# USB-C-Control.net
KiCad netlist of a schematic drawn in Altium Designer
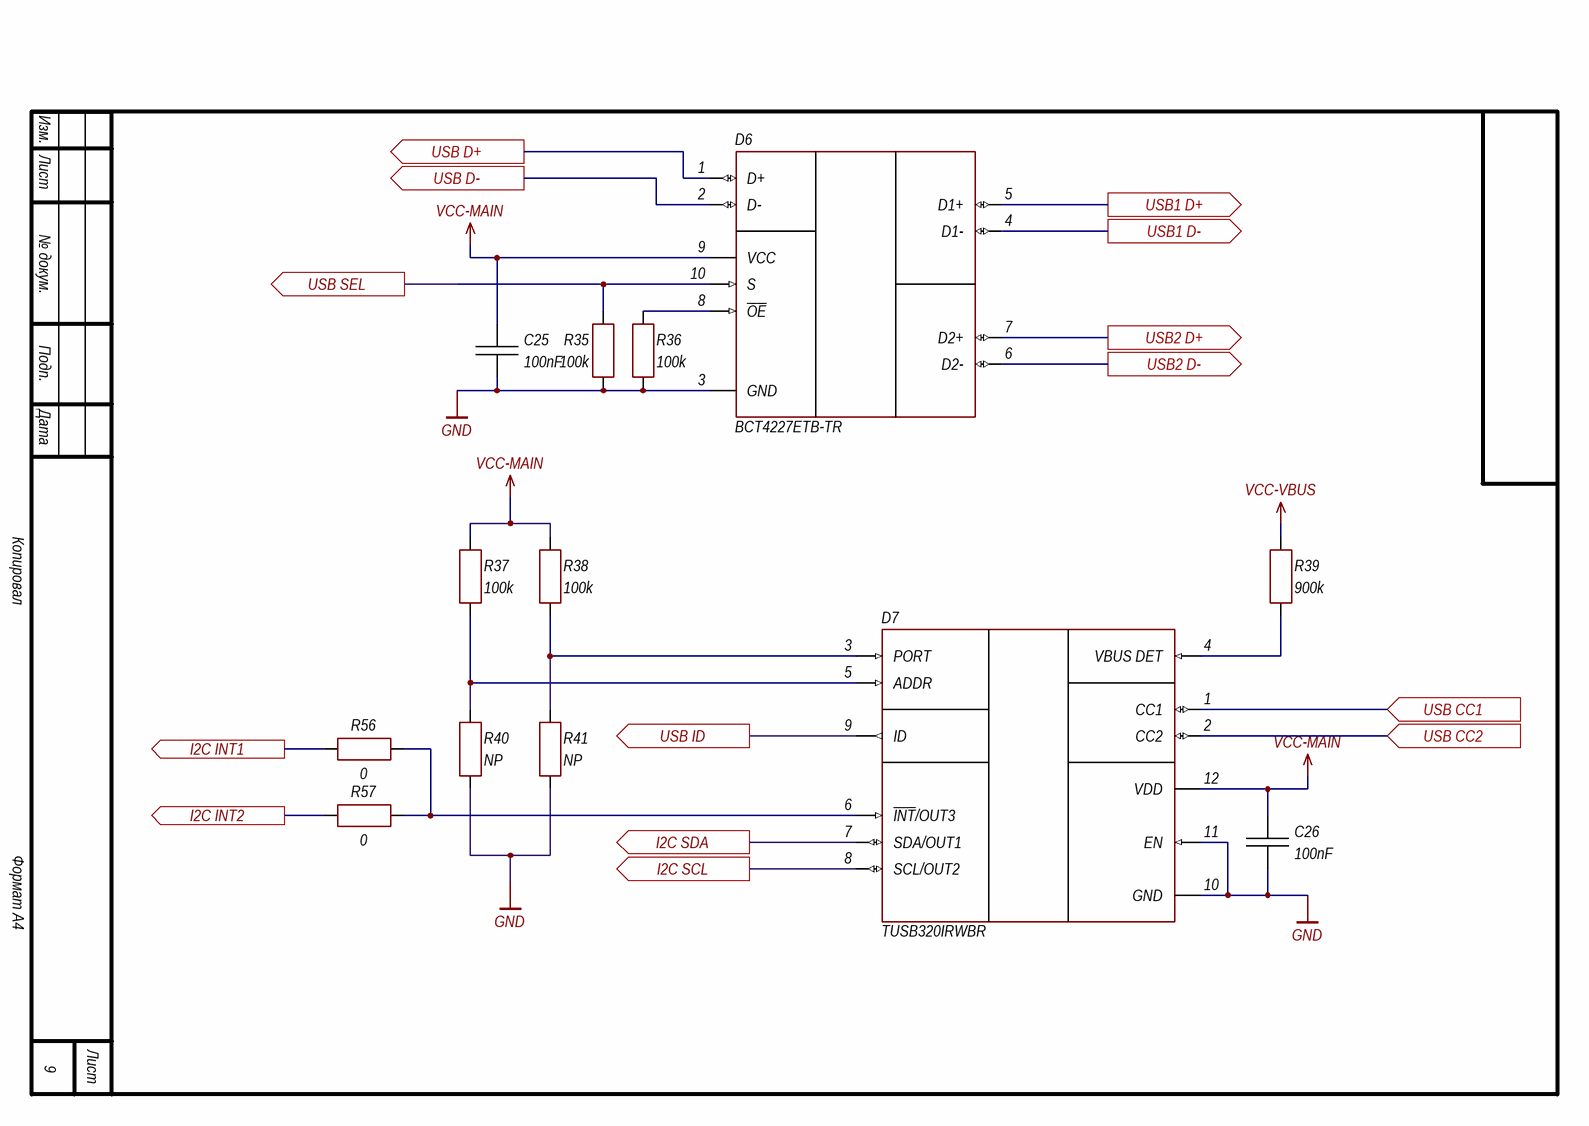
[diagram p0: USB-C-Control.SchDoc]

(export (version "E")
  (design (tool "Eeschema 10.0.6"))
  (components
    (comp (ref "C25") (value "100nF") (footprint "CH0402C") (libsource (lib "Discrete") (part "Capacitor")))
    (comp (ref "C26") (value "100nF") (footprint "CH0402C") (libsource (lib "Discrete") (part "Capacitor")))
    (comp (ref "D6")
      (value "BCT4227ETB-TR")
      (footprint "10-UQFN")
      (description "USB 2.0 1:2 Mux/Demux")
      (fields (field (name "MANUFACTURER") "BROADCHIP") (field (name "MODEL") "BCT4227ETB-TR"))
      (libsource (lib "Interface") (part "BCT4227ETB-TR"))
    )
    (comp (ref "D7")
      (value "TUSB320IRWBR")
      (footprint "12-X2QFN")
      (description "USB-C Port I2C controller (USB OTG)")
      (fields (field (name "MANUFACTURER") "Texas Instruments") (field (name "MODEL") "TUSB320IRWBR"))
      (libsource (lib "Interface") (part "TUSB320"))
    )
    (comp (ref "R35") (value "100k") (footprint "CH0402R") (libsource (lib "Discrete") (part "Resistor")))
    (comp (ref "R36") (value "100k") (footprint "CH0402R") (libsource (lib "") (part "Resistor_1")))
    (comp (ref "R37") (value "100k") (footprint "CH0402R") (libsource (lib "") (part "Resistor_1")))
    (comp (ref "R38") (value "100k") (footprint "CH0402R") (libsource (lib "") (part "Resistor_1")))
    (comp (ref "R39") (value "900k") (footprint "CH0402R") (libsource (lib "") (part "Resistor_1")))
    (comp (ref "R40") (value "NP") (footprint "CH0402R") (libsource (lib "") (part "Resistor_1")))
    (comp (ref "R41") (value "NP") (footprint "CH0402R") (libsource (lib "") (part "Resistor_1")))
    (comp (ref "R56") (value "0") (footprint "CH0402R") (libsource (lib "Discrete") (part "Resistor")))
    (comp (ref "R57") (value "0") (footprint "CH0402R") (libsource (lib "Discrete") (part "Resistor")))
  )
  (nets
    (net (code "1") (name "/I2C INT1") (class "Default")
      (node (ref "R56") (pin "1") (pinfunction "1_1") (pintype "passive"))
    )
    (net (code "2") (name "/I2C INT2") (class "Default")
      (node (ref "R57") (pin "1") (pinfunction "1_1") (pintype "passive"))
    )
    (net (code "3") (name "/I2C SCL") (class "Default")
      (node (ref "D7") (pin "8") (pinfunction "SCL/OUT2_8") (pintype "bidirectional"))
    )
    (net (code "4") (name "/I2C SDA") (class "Default")
      (node (ref "D7") (pin "7") (pinfunction "SDA/OUT1_7") (pintype "bidirectional"))
    )
    (net (code "5") (name "/USB CC1") (class "Default")
      (node (ref "D7") (pin "1") (pinfunction "CC1_1") (pintype "bidirectional"))
    )
    (net (code "6") (name "/USB CC2") (class "Default")
      (node (ref "D7") (pin "2") (pinfunction "CC2_2") (pintype "bidirectional"))
    )
    (net (code "7") (name "/USB D+") (class "Default")
      (node (ref "D6") (pin "1") (pinfunction "D+_1") (pintype "bidirectional"))
    )
    (net (code "8") (name "/USB D-") (class "Default")
      (node (ref "D6") (pin "2") (pinfunction "D-_2") (pintype "bidirectional"))
    )
    (net (code "9") (name "/USB ID") (class "Default")
      (node (ref "D7") (pin "9") (pinfunction "ID_9") (pintype "output"))
    )
    (net (code "10") (name "/USB SEL") (class "Default")
      (node (ref "D6") (pin "10") (pinfunction "S_10") (pintype "input"))
      (node (ref "R35") (pin "2") (pinfunction "2_2") (pintype "passive"))
    )
    (net (code "11") (name "/USB1 D+") (class "Default")
      (node (ref "D6") (pin "5") (pinfunction "D1+_5") (pintype "bidirectional"))
    )
    (net (code "12") (name "/USB1 D-") (class "Default")
      (node (ref "D6") (pin "4") (pinfunction "D1-_4") (pintype "bidirectional"))
    )
    (net (code "13") (name "/USB2 D+") (class "Default")
      (node (ref "D6") (pin "7") (pinfunction "D2+_7") (pintype "bidirectional"))
    )
    (net (code "14") (name "/USB2 D-") (class "Default")
      (node (ref "D6") (pin "6") (pinfunction "D2-_6") (pintype "bidirectional"))
    )
    (net (code "15") (name "GND") (class "Default")
      (node (ref "C25") (pin "1") (pinfunction "1_1") (pintype "passive"))
      (node (ref "C26") (pin "1") (pinfunction "1_1") (pintype "passive"))
      (node (ref "D6") (pin "3") (pinfunction "GND_3") (pintype "power_in"))
      (node (ref "D7") (pin "10") (pinfunction "GND_10") (pintype "power_in"))
      (node (ref "D7") (pin "11") (pinfunction "EN_11") (pintype "input"))
      (node (ref "R35") (pin "1") (pinfunction "1_1") (pintype "passive"))
      (node (ref "R36") (pin "1") (pinfunction "1_1") (pintype "passive"))
      (node (ref "R40") (pin "1") (pinfunction "1_1") (pintype "passive"))
      (node (ref "R41") (pin "1") (pinfunction "1_1") (pintype "passive"))
    )
    (net (code "16") (name "Net-(D6-~{OE})") (class "Default")
      (node (ref "D6") (pin "8") (pinfunction "~{OE}_8") (pintype "input"))
      (node (ref "R36") (pin "2") (pinfunction "2_2") (pintype "passive"))
    )
    (net (code "17") (name "Net-(D7-ADDR)") (class "Default")
      (node (ref "D7") (pin "5") (pinfunction "ADDR_5") (pintype "input"))
      (node (ref "R37") (pin "1") (pinfunction "1_1") (pintype "passive"))
      (node (ref "R40") (pin "2") (pinfunction "2_2") (pintype "passive"))
    )
    (net (code "18") (name "Net-(D7-PORT)") (class "Default")
      (node (ref "D7") (pin "3") (pinfunction "PORT_3") (pintype "input"))
      (node (ref "R38") (pin "1") (pinfunction "1_1") (pintype "passive"))
      (node (ref "R41") (pin "2") (pinfunction "2_2") (pintype "passive"))
    )
    (net (code "19") (name "Net-(D7-VBUS_DET)") (class "Default")
      (node (ref "D7") (pin "4") (pinfunction "VBUS_DET_4") (pintype "input"))
      (node (ref "R39") (pin "1") (pinfunction "1_1") (pintype "passive"))
    )
    (net (code "20") (name "Net-(D7-~{INT}{slash}OUT3)") (class "Default")
      (node (ref "D7") (pin "6") (pinfunction "~{INT}/OUT3_6") (pintype "input"))
      (node (ref "R56") (pin "2") (pinfunction "2_2") (pintype "passive"))
      (node (ref "R57") (pin "2") (pinfunction "2_2") (pintype "passive"))
    )
    (net (code "21") (name "VCC-MAIN") (class "Default")
      (node (ref "C25") (pin "2") (pinfunction "2_2") (pintype "passive"))
      (node (ref "C26") (pin "2") (pinfunction "2_2") (pintype "passive"))
      (node (ref "D6") (pin "9") (pinfunction "VCC_9") (pintype "power_in"))
      (node (ref "D7") (pin "12") (pinfunction "VDD_12") (pintype "power_in"))
      (node (ref "R37") (pin "2") (pinfunction "2_2") (pintype "passive"))
      (node (ref "R38") (pin "2") (pinfunction "2_2") (pintype "passive"))
    )
    (net (code "22") (name "VCC-VBUS") (class "Default")
      (node (ref "R39") (pin "2") (pinfunction "2_2") (pintype "passive"))
    )
  )
)
